# piezo-layer_v0_2-R001.net
KiCad netlist of a schematic drawn in EAGLE
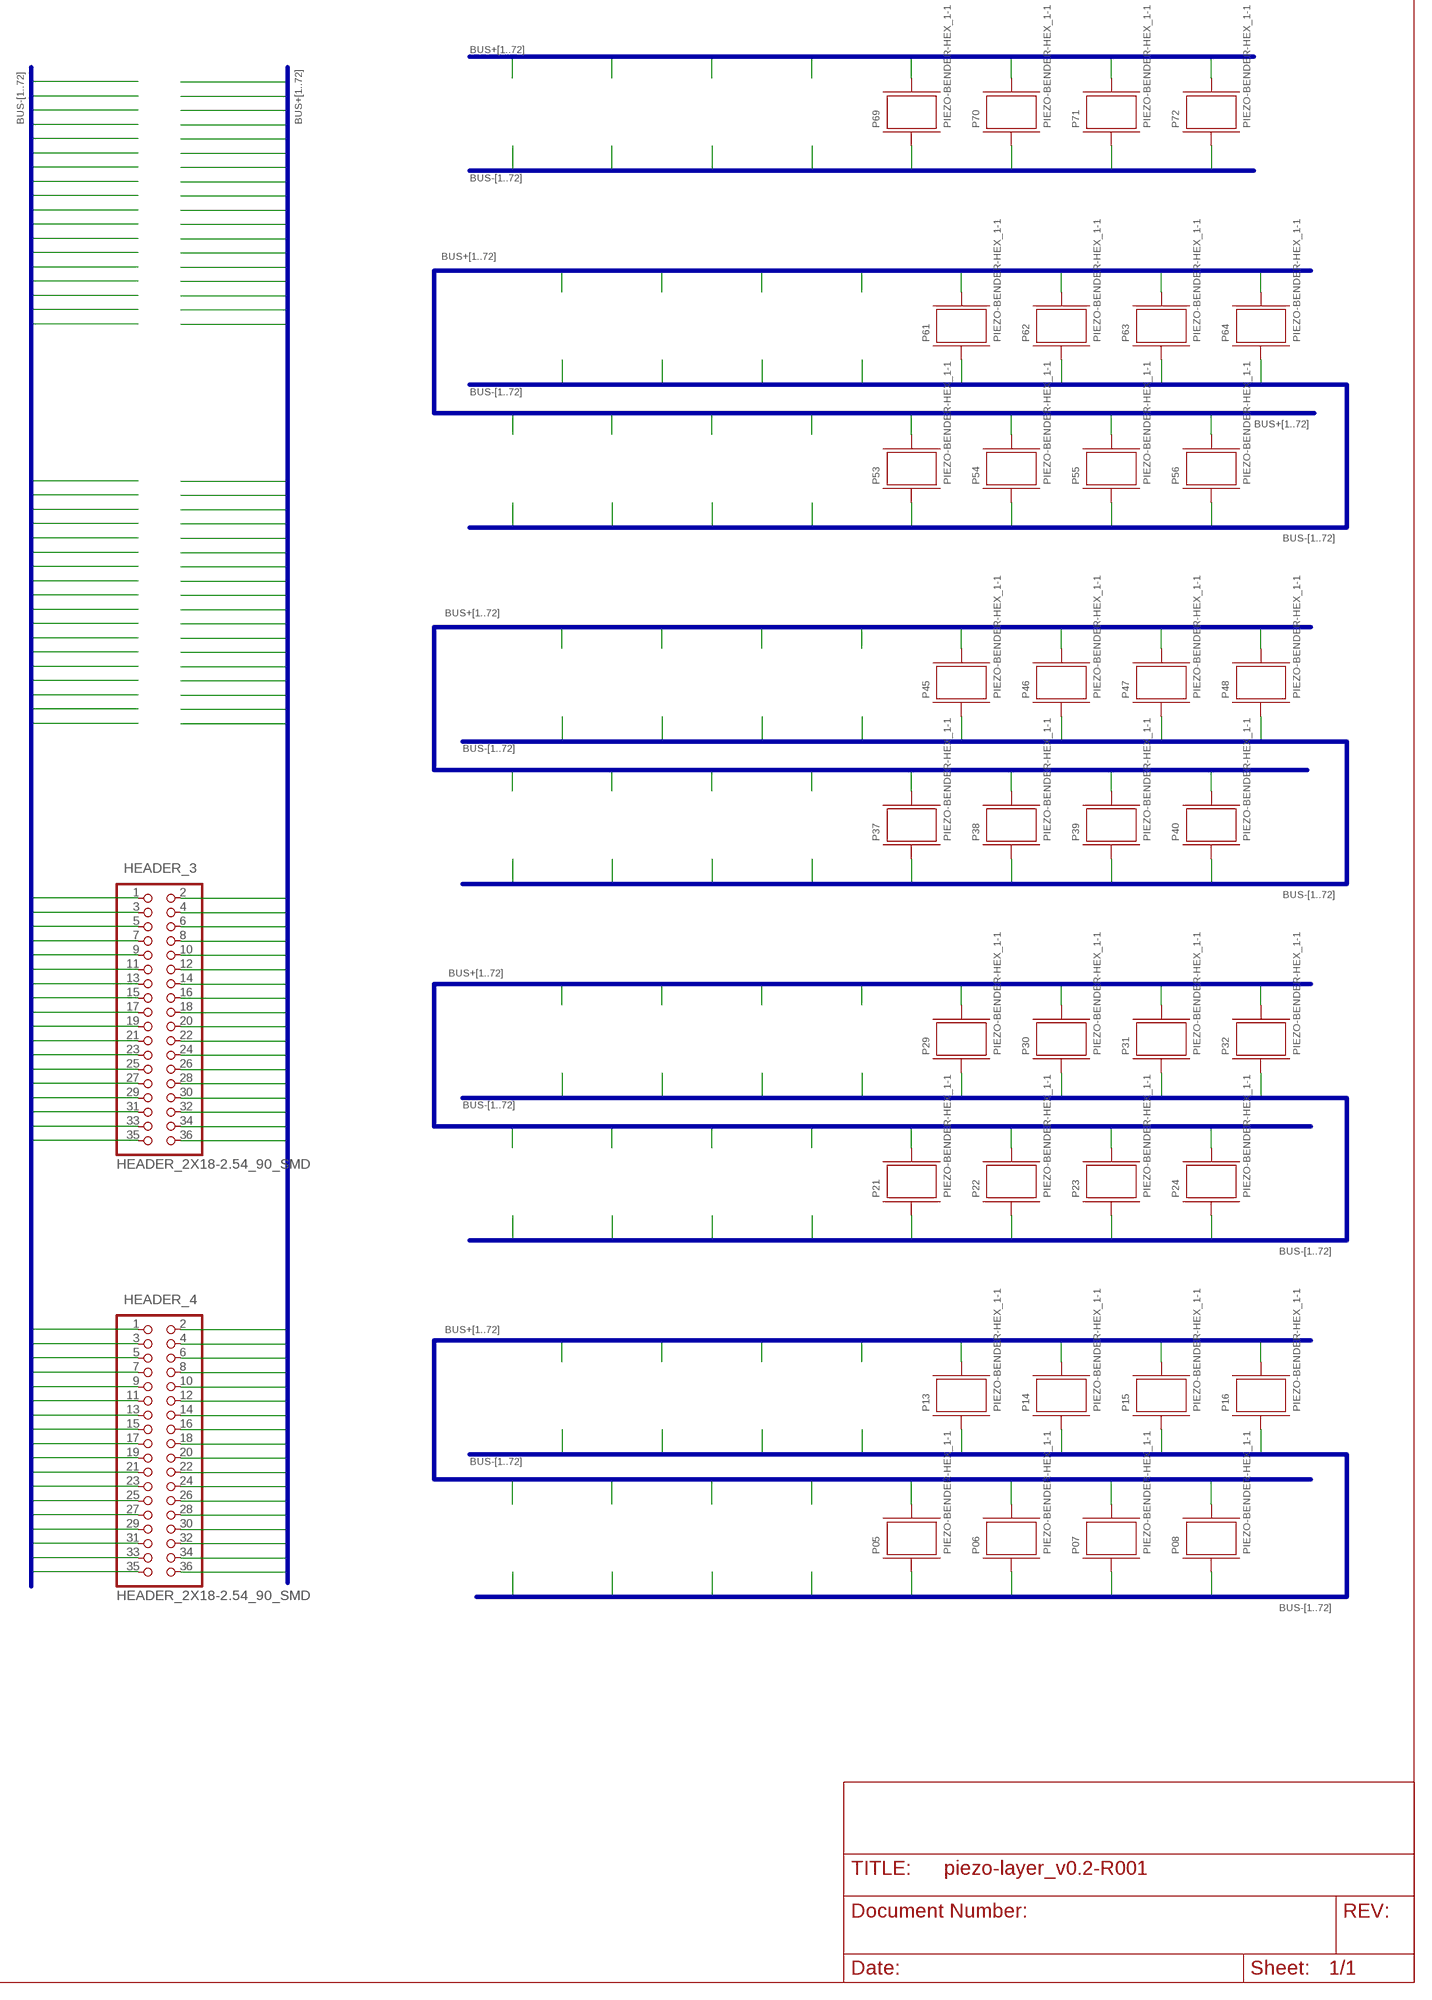
[diagram p0: schematic, sheet 1]

(export (version "E")
  (design (tool "Eeschema 10.0.6"))
  (components
    (comp (ref "HEADER_3")
      (value "HEADER_2X18-2.54_90_SMD")
      (footprint "eagle-import:2X18_2.54_90_SMD")
      (libsource (lib "eagle-import") (part "HEADER_2X18-2.54_90_SMD"))
    )
    (comp (ref "HEADER_4")
      (value "HEADER_2X18-2.54_90_SMD")
      (footprint "eagle-import:2X18_2.54_90_SMD")
      (libsource (lib "eagle-import") (part "HEADER_2X18-2.54_90_SMD"))
    )
    (comp (ref "P05")
      (value "PIEZO-BENDER-HEX_1-1")
      (footprint "eagle-import:PIEZO-BENDER-HEX_16MM_1+_1-")
      (libsource (lib "eagle-import") (part "PIEZO-BENDER-HEX_1-1"))
    )
    (comp (ref "P06")
      (value "PIEZO-BENDER-HEX_1-1")
      (footprint "eagle-import:PIEZO-BENDER-HEX_16MM_1+_1-")
      (libsource (lib "eagle-import") (part "PIEZO-BENDER-HEX_1-1"))
    )
    (comp (ref "P07")
      (value "PIEZO-BENDER-HEX_1-1")
      (footprint "eagle-import:PIEZO-BENDER-HEX_16MM_1+_1-")
      (libsource (lib "eagle-import") (part "PIEZO-BENDER-HEX_1-1"))
    )
    (comp (ref "P08")
      (value "PIEZO-BENDER-HEX_1-1")
      (footprint "eagle-import:PIEZO-BENDER-HEX_16MM_1+_1-")
      (libsource (lib "eagle-import") (part "PIEZO-BENDER-HEX_1-1"))
    )
    (comp (ref "P13")
      (value "PIEZO-BENDER-HEX_1-1")
      (footprint "eagle-import:PIEZO-BENDER-HEX_16MM_1+_1-")
      (libsource (lib "eagle-import") (part "PIEZO-BENDER-HEX_1-1"))
    )
    (comp (ref "P14")
      (value "PIEZO-BENDER-HEX_1-1")
      (footprint "eagle-import:PIEZO-BENDER-HEX_16MM_1+_1-")
      (libsource (lib "eagle-import") (part "PIEZO-BENDER-HEX_1-1"))
    )
    (comp (ref "P15")
      (value "PIEZO-BENDER-HEX_1-1")
      (footprint "eagle-import:PIEZO-BENDER-HEX_16MM_1+_1-")
      (libsource (lib "eagle-import") (part "PIEZO-BENDER-HEX_1-1"))
    )
    (comp (ref "P16")
      (value "PIEZO-BENDER-HEX_1-1")
      (footprint "eagle-import:PIEZO-BENDER-HEX_16MM_1+_1-")
      (libsource (lib "eagle-import") (part "PIEZO-BENDER-HEX_1-1"))
    )
    (comp (ref "P21")
      (value "PIEZO-BENDER-HEX_1-1")
      (footprint "eagle-import:PIEZO-BENDER-HEX_16MM_1+_1-")
      (libsource (lib "eagle-import") (part "PIEZO-BENDER-HEX_1-1"))
    )
    (comp (ref "P22")
      (value "PIEZO-BENDER-HEX_1-1")
      (footprint "eagle-import:PIEZO-BENDER-HEX_16MM_1+_1-")
      (libsource (lib "eagle-import") (part "PIEZO-BENDER-HEX_1-1"))
    )
    (comp (ref "P23")
      (value "PIEZO-BENDER-HEX_1-1")
      (footprint "eagle-import:PIEZO-BENDER-HEX_16MM_1+_1-")
      (libsource (lib "eagle-import") (part "PIEZO-BENDER-HEX_1-1"))
    )
    (comp (ref "P24")
      (value "PIEZO-BENDER-HEX_1-1")
      (footprint "eagle-import:PIEZO-BENDER-HEX_16MM_1+_1-")
      (libsource (lib "eagle-import") (part "PIEZO-BENDER-HEX_1-1"))
    )
    (comp (ref "P29")
      (value "PIEZO-BENDER-HEX_1-1")
      (footprint "eagle-import:PIEZO-BENDER-HEX_16MM_1+_1-")
      (libsource (lib "eagle-import") (part "PIEZO-BENDER-HEX_1-1"))
    )
    (comp (ref "P30")
      (value "PIEZO-BENDER-HEX_1-1")
      (footprint "eagle-import:PIEZO-BENDER-HEX_16MM_1+_1-")
      (libsource (lib "eagle-import") (part "PIEZO-BENDER-HEX_1-1"))
    )
    (comp (ref "P31")
      (value "PIEZO-BENDER-HEX_1-1")
      (footprint "eagle-import:PIEZO-BENDER-HEX_16MM_1+_1-")
      (libsource (lib "eagle-import") (part "PIEZO-BENDER-HEX_1-1"))
    )
    (comp (ref "P32")
      (value "PIEZO-BENDER-HEX_1-1")
      (footprint "eagle-import:PIEZO-BENDER-HEX_16MM_1+_1-")
      (libsource (lib "eagle-import") (part "PIEZO-BENDER-HEX_1-1"))
    )
    (comp (ref "P37")
      (value "PIEZO-BENDER-HEX_1-1")
      (footprint "eagle-import:PIEZO-BENDER-HEX_16MM_1+_1-")
      (libsource (lib "eagle-import") (part "PIEZO-BENDER-HEX_1-1"))
    )
    (comp (ref "P38")
      (value "PIEZO-BENDER-HEX_1-1")
      (footprint "eagle-import:PIEZO-BENDER-HEX_16MM_1+_1-")
      (libsource (lib "eagle-import") (part "PIEZO-BENDER-HEX_1-1"))
    )
    (comp (ref "P39")
      (value "PIEZO-BENDER-HEX_1-1")
      (footprint "eagle-import:PIEZO-BENDER-HEX_16MM_1+_1-")
      (libsource (lib "eagle-import") (part "PIEZO-BENDER-HEX_1-1"))
    )
    (comp (ref "P40")
      (value "PIEZO-BENDER-HEX_1-1")
      (footprint "eagle-import:PIEZO-BENDER-HEX_16MM_1+_1-")
      (libsource (lib "eagle-import") (part "PIEZO-BENDER-HEX_1-1"))
    )
    (comp (ref "P45")
      (value "PIEZO-BENDER-HEX_1-1")
      (footprint "eagle-import:PIEZO-BENDER-HEX_16MM_1+_1-")
      (libsource (lib "eagle-import") (part "PIEZO-BENDER-HEX_1-1"))
    )
    (comp (ref "P46")
      (value "PIEZO-BENDER-HEX_1-1")
      (footprint "eagle-import:PIEZO-BENDER-HEX_16MM_1+_1-")
      (libsource (lib "eagle-import") (part "PIEZO-BENDER-HEX_1-1"))
    )
    (comp (ref "P47")
      (value "PIEZO-BENDER-HEX_1-1")
      (footprint "eagle-import:PIEZO-BENDER-HEX_16MM_1+_1-")
      (libsource (lib "eagle-import") (part "PIEZO-BENDER-HEX_1-1"))
    )
    (comp (ref "P48")
      (value "PIEZO-BENDER-HEX_1-1")
      (footprint "eagle-import:PIEZO-BENDER-HEX_16MM_1+_1-")
      (libsource (lib "eagle-import") (part "PIEZO-BENDER-HEX_1-1"))
    )
    (comp (ref "P53")
      (value "PIEZO-BENDER-HEX_1-1")
      (footprint "eagle-import:PIEZO-BENDER-HEX_16MM_1+_1-")
      (libsource (lib "eagle-import") (part "PIEZO-BENDER-HEX_1-1"))
    )
    (comp (ref "P54")
      (value "PIEZO-BENDER-HEX_1-1")
      (footprint "eagle-import:PIEZO-BENDER-HEX_16MM_1+_1-")
      (libsource (lib "eagle-import") (part "PIEZO-BENDER-HEX_1-1"))
    )
    (comp (ref "P55")
      (value "PIEZO-BENDER-HEX_1-1")
      (footprint "eagle-import:PIEZO-BENDER-HEX_16MM_1+_1-")
      (libsource (lib "eagle-import") (part "PIEZO-BENDER-HEX_1-1"))
    )
    (comp (ref "P56")
      (value "PIEZO-BENDER-HEX_1-1")
      (footprint "eagle-import:PIEZO-BENDER-HEX_16MM_1+_1-")
      (libsource (lib "eagle-import") (part "PIEZO-BENDER-HEX_1-1"))
    )
    (comp (ref "P61")
      (value "PIEZO-BENDER-HEX_1-1")
      (footprint "eagle-import:PIEZO-BENDER-HEX_16MM_1+_1-")
      (libsource (lib "eagle-import") (part "PIEZO-BENDER-HEX_1-1"))
    )
    (comp (ref "P62")
      (value "PIEZO-BENDER-HEX_1-1")
      (footprint "eagle-import:PIEZO-BENDER-HEX_16MM_1+_1-")
      (libsource (lib "eagle-import") (part "PIEZO-BENDER-HEX_1-1"))
    )
    (comp (ref "P63")
      (value "PIEZO-BENDER-HEX_1-1")
      (footprint "eagle-import:PIEZO-BENDER-HEX_16MM_1+_1-")
      (libsource (lib "eagle-import") (part "PIEZO-BENDER-HEX_1-1"))
    )
    (comp (ref "P64")
      (value "PIEZO-BENDER-HEX_1-1")
      (footprint "eagle-import:PIEZO-BENDER-HEX_16MM_1+_1-")
      (libsource (lib "eagle-import") (part "PIEZO-BENDER-HEX_1-1"))
    )
    (comp (ref "P69")
      (value "PIEZO-BENDER-HEX_1-1")
      (footprint "eagle-import:PIEZO-BENDER-HEX_16MM_1+_1-")
      (libsource (lib "eagle-import") (part "PIEZO-BENDER-HEX_1-1"))
    )
    (comp (ref "P70")
      (value "PIEZO-BENDER-HEX_1-1")
      (footprint "eagle-import:PIEZO-BENDER-HEX_16MM_1+_1-")
      (libsource (lib "eagle-import") (part "PIEZO-BENDER-HEX_1-1"))
    )
    (comp (ref "P71")
      (value "PIEZO-BENDER-HEX_1-1")
      (footprint "eagle-import:PIEZO-BENDER-HEX_16MM_1+_1-")
      (libsource (lib "eagle-import") (part "PIEZO-BENDER-HEX_1-1"))
    )
    (comp (ref "P72")
      (value "PIEZO-BENDER-HEX_1-1")
      (footprint "eagle-import:PIEZO-BENDER-HEX_16MM_1+_1-")
      (libsource (lib "eagle-import") (part "PIEZO-BENDER-HEX_1-1"))
    )
  )
  (nets
    (net (code "5") (name "/BUS+5") (class "Default")
      (node (ref "HEADER_3") (pin "18") (pinfunction "18_18") (pintype "passive"))
      (node (ref "P05") (pin "TIP1") (pinfunction "+_1_TIP1") (pintype "bidirectional"))
    )
    (net (code "6") (name "/BUS+6") (class "Default")
      (node (ref "HEADER_3") (pin "36") (pinfunction "36_36") (pintype "passive"))
      (node (ref "P06") (pin "TIP1") (pinfunction "+_1_TIP1") (pintype "bidirectional"))
    )
    (net (code "7") (name "/BUS+7") (class "Default")
      (node (ref "HEADER_4") (pin "18") (pinfunction "18_18") (pintype "passive"))
      (node (ref "P07") (pin "TIP1") (pinfunction "+_1_TIP1") (pintype "bidirectional"))
    )
    (net (code "8") (name "/BUS+8") (class "Default")
      (node (ref "HEADER_4") (pin "36") (pinfunction "36_36") (pintype "passive"))
      (node (ref "P08") (pin "TIP1") (pinfunction "+_1_TIP1") (pintype "bidirectional"))
    )
    (net (code "13") (name "/BUS+13") (class "Default")
      (node (ref "HEADER_3") (pin "16") (pinfunction "16_16") (pintype "passive"))
      (node (ref "P13") (pin "TIP1") (pinfunction "+_1_TIP1") (pintype "bidirectional"))
    )
    (net (code "14") (name "/BUS+14") (class "Default")
      (node (ref "HEADER_3") (pin "34") (pinfunction "34_34") (pintype "passive"))
      (node (ref "P14") (pin "TIP1") (pinfunction "+_1_TIP1") (pintype "bidirectional"))
    )
    (net (code "15") (name "/BUS+15") (class "Default")
      (node (ref "HEADER_4") (pin "16") (pinfunction "16_16") (pintype "passive"))
      (node (ref "P15") (pin "TIP1") (pinfunction "+_1_TIP1") (pintype "bidirectional"))
    )
    (net (code "16") (name "/BUS+16") (class "Default")
      (node (ref "HEADER_4") (pin "34") (pinfunction "34_34") (pintype "passive"))
      (node (ref "P16") (pin "TIP1") (pinfunction "+_1_TIP1") (pintype "bidirectional"))
    )
    (net (code "21") (name "/BUS+21") (class "Default")
      (node (ref "HEADER_3") (pin "14") (pinfunction "14_14") (pintype "passive"))
      (node (ref "P21") (pin "TIP1") (pinfunction "+_1_TIP1") (pintype "bidirectional"))
    )
    (net (code "22") (name "/BUS+22") (class "Default")
      (node (ref "HEADER_3") (pin "32") (pinfunction "32_32") (pintype "passive"))
      (node (ref "P22") (pin "TIP1") (pinfunction "+_1_TIP1") (pintype "bidirectional"))
    )
    (net (code "23") (name "/BUS+23") (class "Default")
      (node (ref "HEADER_4") (pin "14") (pinfunction "14_14") (pintype "passive"))
      (node (ref "P23") (pin "TIP1") (pinfunction "+_1_TIP1") (pintype "bidirectional"))
    )
    (net (code "24") (name "/BUS+24") (class "Default")
      (node (ref "HEADER_4") (pin "32") (pinfunction "32_32") (pintype "passive"))
      (node (ref "P24") (pin "TIP1") (pinfunction "+_1_TIP1") (pintype "bidirectional"))
    )
    (net (code "29") (name "/BUS+29") (class "Default")
      (node (ref "HEADER_3") (pin "12") (pinfunction "12_12") (pintype "passive"))
      (node (ref "P29") (pin "TIP1") (pinfunction "+_1_TIP1") (pintype "bidirectional"))
    )
    (net (code "30") (name "/BUS+30") (class "Default")
      (node (ref "HEADER_3") (pin "30") (pinfunction "30_30") (pintype "passive"))
      (node (ref "P30") (pin "TIP1") (pinfunction "+_1_TIP1") (pintype "bidirectional"))
    )
    (net (code "31") (name "/BUS+31") (class "Default")
      (node (ref "HEADER_4") (pin "12") (pinfunction "12_12") (pintype "passive"))
      (node (ref "P31") (pin "TIP1") (pinfunction "+_1_TIP1") (pintype "bidirectional"))
    )
    (net (code "32") (name "/BUS+32") (class "Default")
      (node (ref "HEADER_4") (pin "30") (pinfunction "30_30") (pintype "passive"))
      (node (ref "P32") (pin "TIP1") (pinfunction "+_1_TIP1") (pintype "bidirectional"))
    )
    (net (code "37") (name "/BUS+37") (class "Default")
      (node (ref "HEADER_3") (pin "10") (pinfunction "10_10") (pintype "passive"))
      (node (ref "P37") (pin "TIP1") (pinfunction "+_1_TIP1") (pintype "bidirectional"))
    )
    (net (code "38") (name "/BUS+38") (class "Default")
      (node (ref "HEADER_3") (pin "28") (pinfunction "28_28") (pintype "passive"))
      (node (ref "P38") (pin "TIP1") (pinfunction "+_1_TIP1") (pintype "bidirectional"))
    )
    (net (code "39") (name "/BUS+39") (class "Default")
      (node (ref "HEADER_4") (pin "10") (pinfunction "10_10") (pintype "passive"))
      (node (ref "P39") (pin "TIP1") (pinfunction "+_1_TIP1") (pintype "bidirectional"))
    )
    (net (code "40") (name "/BUS+40") (class "Default")
      (node (ref "HEADER_4") (pin "28") (pinfunction "28_28") (pintype "passive"))
      (node (ref "P40") (pin "TIP1") (pinfunction "+_1_TIP1") (pintype "bidirectional"))
    )
    (net (code "45") (name "/BUS+45") (class "Default")
      (node (ref "HEADER_3") (pin "8") (pinfunction "8_8") (pintype "passive"))
      (node (ref "P45") (pin "TIP1") (pinfunction "+_1_TIP1") (pintype "bidirectional"))
    )
    (net (code "46") (name "/BUS+46") (class "Default")
      (node (ref "HEADER_3") (pin "26") (pinfunction "26_26") (pintype "passive"))
      (node (ref "P46") (pin "TIP1") (pinfunction "+_1_TIP1") (pintype "bidirectional"))
    )
    (net (code "47") (name "/BUS+47") (class "Default")
      (node (ref "HEADER_4") (pin "8") (pinfunction "8_8") (pintype "passive"))
      (node (ref "P47") (pin "TIP1") (pinfunction "+_1_TIP1") (pintype "bidirectional"))
    )
    (net (code "48") (name "/BUS+48") (class "Default")
      (node (ref "HEADER_4") (pin "26") (pinfunction "26_26") (pintype "passive"))
      (node (ref "P48") (pin "TIP1") (pinfunction "+_1_TIP1") (pintype "bidirectional"))
    )
    (net (code "53") (name "/BUS+53") (class "Default")
      (node (ref "HEADER_3") (pin "6") (pinfunction "6_6") (pintype "passive"))
      (node (ref "P53") (pin "TIP1") (pinfunction "+_1_TIP1") (pintype "bidirectional"))
    )
    (net (code "54") (name "/BUS+54") (class "Default")
      (node (ref "HEADER_3") (pin "24") (pinfunction "24_24") (pintype "passive"))
      (node (ref "P54") (pin "TIP1") (pinfunction "+_1_TIP1") (pintype "bidirectional"))
    )
    (net (code "55") (name "/BUS+55") (class "Default")
      (node (ref "HEADER_4") (pin "6") (pinfunction "6_6") (pintype "passive"))
      (node (ref "P55") (pin "TIP1") (pinfunction "+_1_TIP1") (pintype "bidirectional"))
    )
    (net (code "56") (name "/BUS+56") (class "Default")
      (node (ref "HEADER_4") (pin "24") (pinfunction "24_24") (pintype "passive"))
      (node (ref "P56") (pin "TIP1") (pinfunction "+_1_TIP1") (pintype "bidirectional"))
    )
    (net (code "61") (name "/BUS+61") (class "Default")
      (node (ref "HEADER_3") (pin "4") (pinfunction "4_4") (pintype "passive"))
      (node (ref "P61") (pin "TIP1") (pinfunction "+_1_TIP1") (pintype "bidirectional"))
    )
    (net (code "62") (name "/BUS+62") (class "Default")
      (node (ref "HEADER_3") (pin "22") (pinfunction "22_22") (pintype "passive"))
      (node (ref "P62") (pin "TIP1") (pinfunction "+_1_TIP1") (pintype "bidirectional"))
    )
    (net (code "63") (name "/BUS+63") (class "Default")
      (node (ref "HEADER_4") (pin "4") (pinfunction "4_4") (pintype "passive"))
      (node (ref "P63") (pin "TIP1") (pinfunction "+_1_TIP1") (pintype "bidirectional"))
    )
    (net (code "64") (name "/BUS+64") (class "Default")
      (node (ref "HEADER_4") (pin "22") (pinfunction "22_22") (pintype "passive"))
      (node (ref "P64") (pin "TIP1") (pinfunction "+_1_TIP1") (pintype "bidirectional"))
    )
    (net (code "69") (name "/BUS+69") (class "Default")
      (node (ref "HEADER_3") (pin "2") (pinfunction "2_2") (pintype "passive"))
      (node (ref "P69") (pin "TIP1") (pinfunction "+_1_TIP1") (pintype "bidirectional"))
    )
    (net (code "70") (name "/BUS+70") (class "Default")
      (node (ref "HEADER_3") (pin "20") (pinfunction "20_20") (pintype "passive"))
      (node (ref "P70") (pin "TIP1") (pinfunction "+_1_TIP1") (pintype "bidirectional"))
    )
    (net (code "71") (name "/BUS+71") (class "Default")
      (node (ref "HEADER_4") (pin "2") (pinfunction "2_2") (pintype "passive"))
      (node (ref "P71") (pin "TIP1") (pinfunction "+_1_TIP1") (pintype "bidirectional"))
    )
    (net (code "72") (name "/BUS+72") (class "Default")
      (node (ref "HEADER_4") (pin "20") (pinfunction "20_20") (pintype "passive"))
      (node (ref "P72") (pin "TIP1") (pinfunction "+_1_TIP1") (pintype "bidirectional"))
    )
    (net (code "78") (name "/BUS-5") (class "Default")
      (node (ref "HEADER_3") (pin "17") (pinfunction "17_17") (pintype "passive"))
      (node (ref "P05") (pin "PAD1") (pinfunction "-_1_PAD1") (pintype "bidirectional"))
    )
    (net (code "79") (name "/BUS-6") (class "Default")
      (node (ref "HEADER_3") (pin "35") (pinfunction "35_35") (pintype "passive"))
      (node (ref "P06") (pin "PAD1") (pinfunction "-_1_PAD1") (pintype "bidirectional"))
    )
    (net (code "80") (name "/BUS-7") (class "Default")
      (node (ref "HEADER_4") (pin "17") (pinfunction "17_17") (pintype "passive"))
      (node (ref "P07") (pin "PAD1") (pinfunction "-_1_PAD1") (pintype "bidirectional"))
    )
    (net (code "81") (name "/BUS-8") (class "Default")
      (node (ref "HEADER_4") (pin "35") (pinfunction "35_35") (pintype "passive"))
      (node (ref "P08") (pin "PAD1") (pinfunction "-_1_PAD1") (pintype "bidirectional"))
    )
    (net (code "86") (name "/BUS-13") (class "Default")
      (node (ref "HEADER_3") (pin "15") (pinfunction "15_15") (pintype "passive"))
      (node (ref "P13") (pin "PAD1") (pinfunction "-_1_PAD1") (pintype "bidirectional"))
    )
    (net (code "87") (name "/BUS-14") (class "Default")
      (node (ref "HEADER_3") (pin "33") (pinfunction "33_33") (pintype "passive"))
      (node (ref "P14") (pin "PAD1") (pinfunction "-_1_PAD1") (pintype "bidirectional"))
    )
    (net (code "88") (name "/BUS-15") (class "Default")
      (node (ref "HEADER_4") (pin "15") (pinfunction "15_15") (pintype "passive"))
      (node (ref "P15") (pin "PAD1") (pinfunction "-_1_PAD1") (pintype "bidirectional"))
    )
    (net (code "89") (name "/BUS-16") (class "Default")
      (node (ref "HEADER_4") (pin "33") (pinfunction "33_33") (pintype "passive"))
      (node (ref "P16") (pin "PAD1") (pinfunction "-_1_PAD1") (pintype "bidirectional"))
    )
    (net (code "94") (name "/BUS-21") (class "Default")
      (node (ref "HEADER_3") (pin "13") (pinfunction "13_13") (pintype "passive"))
      (node (ref "P21") (pin "PAD1") (pinfunction "-_1_PAD1") (pintype "bidirectional"))
    )
    (net (code "95") (name "/BUS-22") (class "Default")
      (node (ref "HEADER_3") (pin "31") (pinfunction "31_31") (pintype "passive"))
      (node (ref "P22") (pin "PAD1") (pinfunction "-_1_PAD1") (pintype "bidirectional"))
    )
    (net (code "96") (name "/BUS-23") (class "Default")
      (node (ref "HEADER_4") (pin "13") (pinfunction "13_13") (pintype "passive"))
      (node (ref "P23") (pin "PAD1") (pinfunction "-_1_PAD1") (pintype "bidirectional"))
    )
    (net (code "97") (name "/BUS-24") (class "Default")
      (node (ref "HEADER_4") (pin "31") (pinfunction "31_31") (pintype "passive"))
      (node (ref "P24") (pin "PAD1") (pinfunction "-_1_PAD1") (pintype "bidirectional"))
    )
    (net (code "102") (name "/BUS-29") (class "Default")
      (node (ref "HEADER_3") (pin "11") (pinfunction "11_11") (pintype "passive"))
      (node (ref "P29") (pin "PAD1") (pinfunction "-_1_PAD1") (pintype "bidirectional"))
    )
    (net (code "103") (name "/BUS-30") (class "Default")
      (node (ref "HEADER_3") (pin "29") (pinfunction "29_29") (pintype "passive"))
      (node (ref "P30") (pin "PAD1") (pinfunction "-_1_PAD1") (pintype "bidirectional"))
    )
    (net (code "104") (name "/BUS-31") (class "Default")
      (node (ref "HEADER_4") (pin "11") (pinfunction "11_11") (pintype "passive"))
      (node (ref "P31") (pin "PAD1") (pinfunction "-_1_PAD1") (pintype "bidirectional"))
    )
    (net (code "105") (name "/BUS-32") (class "Default")
      (node (ref "HEADER_4") (pin "29") (pinfunction "29_29") (pintype "passive"))
      (node (ref "P32") (pin "PAD1") (pinfunction "-_1_PAD1") (pintype "bidirectional"))
    )
    (net (code "110") (name "/BUS-37") (class "Default")
      (node (ref "HEADER_3") (pin "9") (pinfunction "9_9") (pintype "passive"))
      (node (ref "P37") (pin "PAD1") (pinfunction "-_1_PAD1") (pintype "bidirectional"))
    )
    (net (code "111") (name "/BUS-38") (class "Default")
      (node (ref "HEADER_3") (pin "27") (pinfunction "27_27") (pintype "passive"))
      (node (ref "P38") (pin "PAD1") (pinfunction "-_1_PAD1") (pintype "bidirectional"))
    )
    (net (code "112") (name "/BUS-39") (class "Default")
      (node (ref "HEADER_4") (pin "9") (pinfunction "9_9") (pintype "passive"))
      (node (ref "P39") (pin "PAD1") (pinfunction "-_1_PAD1") (pintype "bidirectional"))
    )
    (net (code "113") (name "/BUS-40") (class "Default")
      (node (ref "HEADER_4") (pin "27") (pinfunction "27_27") (pintype "passive"))
      (node (ref "P40") (pin "PAD1") (pinfunction "-_1_PAD1") (pintype "bidirectional"))
    )
    (net (code "118") (name "/BUS-45") (class "Default")
      (node (ref "HEADER_3") (pin "7") (pinfunction "7_7") (pintype "passive"))
      (node (ref "P45") (pin "PAD1") (pinfunction "-_1_PAD1") (pintype "bidirectional"))
    )
    (net (code "119") (name "/BUS-46") (class "Default")
      (node (ref "HEADER_3") (pin "25") (pinfunction "25_25") (pintype "passive"))
      (node (ref "P46") (pin "PAD1") (pinfunction "-_1_PAD1") (pintype "bidirectional"))
    )
    (net (code "120") (name "/BUS-47") (class "Default")
      (node (ref "HEADER_4") (pin "7") (pinfunction "7_7") (pintype "passive"))
      (node (ref "P47") (pin "PAD1") (pinfunction "-_1_PAD1") (pintype "bidirectional"))
    )
    (net (code "121") (name "/BUS-48") (class "Default")
      (node (ref "HEADER_4") (pin "25") (pinfunction "25_25") (pintype "passive"))
      (node (ref "P48") (pin "PAD1") (pinfunction "-_1_PAD1") (pintype "bidirectional"))
    )
    (net (code "126") (name "/BUS-53") (class "Default")
      (node (ref "HEADER_3") (pin "5") (pinfunction "5_5") (pintype "passive"))
      (node (ref "P53") (pin "PAD1") (pinfunction "-_1_PAD1") (pintype "bidirectional"))
    )
    (net (code "127") (name "/BUS-54") (class "Default")
      (node (ref "HEADER_3") (pin "23") (pinfunction "23_23") (pintype "passive"))
      (node (ref "P54") (pin "PAD1") (pinfunction "-_1_PAD1") (pintype "bidirectional"))
    )
    (net (code "128") (name "/BUS-55") (class "Default")
      (node (ref "HEADER_4") (pin "5") (pinfunction "5_5") (pintype "passive"))
      (node (ref "P55") (pin "PAD1") (pinfunction "-_1_PAD1") (pintype "bidirectional"))
    )
    (net (code "129") (name "/BUS-56") (class "Default")
      (node (ref "HEADER_4") (pin "23") (pinfunction "23_23") (pintype "passive"))
      (node (ref "P56") (pin "PAD1") (pinfunction "-_1_PAD1") (pintype "bidirectional"))
    )
    (net (code "134") (name "/BUS-61") (class "Default")
      (node (ref "HEADER_3") (pin "3") (pinfunction "3_3") (pintype "passive"))
      (node (ref "P61") (pin "PAD1") (pinfunction "-_1_PAD1") (pintype "bidirectional"))
    )
    (net (code "135") (name "/BUS-62") (class "Default")
      (node (ref "HEADER_3") (pin "21") (pinfunction "21_21") (pintype "passive"))
      (node (ref "P62") (pin "PAD1") (pinfunction "-_1_PAD1") (pintype "bidirectional"))
    )
    (net (code "136") (name "/BUS-63") (class "Default")
      (node (ref "HEADER_4") (pin "3") (pinfunction "3_3") (pintype "passive"))
      (node (ref "P63") (pin "PAD1") (pinfunction "-_1_PAD1") (pintype "bidirectional"))
    )
    (net (code "137") (name "/BUS-64") (class "Default")
      (node (ref "HEADER_4") (pin "21") (pinfunction "21_21") (pintype "passive"))
      (node (ref "P64") (pin "PAD1") (pinfunction "-_1_PAD1") (pintype "bidirectional"))
    )
    (net (code "142") (name "/BUS-69") (class "Default")
      (node (ref "HEADER_3") (pin "1") (pinfunction "1_1") (pintype "passive"))
      (node (ref "P69") (pin "PAD1") (pinfunction "-_1_PAD1") (pintype "bidirectional"))
    )
    (net (code "143") (name "/BUS-70") (class "Default")
      (node (ref "HEADER_3") (pin "19") (pinfunction "19_19") (pintype "passive"))
      (node (ref "P70") (pin "PAD1") (pinfunction "-_1_PAD1") (pintype "bidirectional"))
    )
    (net (code "144") (name "/BUS-71") (class "Default")
      (node (ref "HEADER_4") (pin "1") (pinfunction "1_1") (pintype "passive"))
      (node (ref "P71") (pin "PAD1") (pinfunction "-_1_PAD1") (pintype "bidirectional"))
    )
    (net (code "145") (name "/BUS-72") (class "Default")
      (node (ref "HEADER_4") (pin "19") (pinfunction "19_19") (pintype "passive"))
      (node (ref "P72") (pin "PAD1") (pinfunction "-_1_PAD1") (pintype "bidirectional"))
    )
  )
)
